# Decawave.net
KiCad netlist of a schematic drawn in Altium Designer
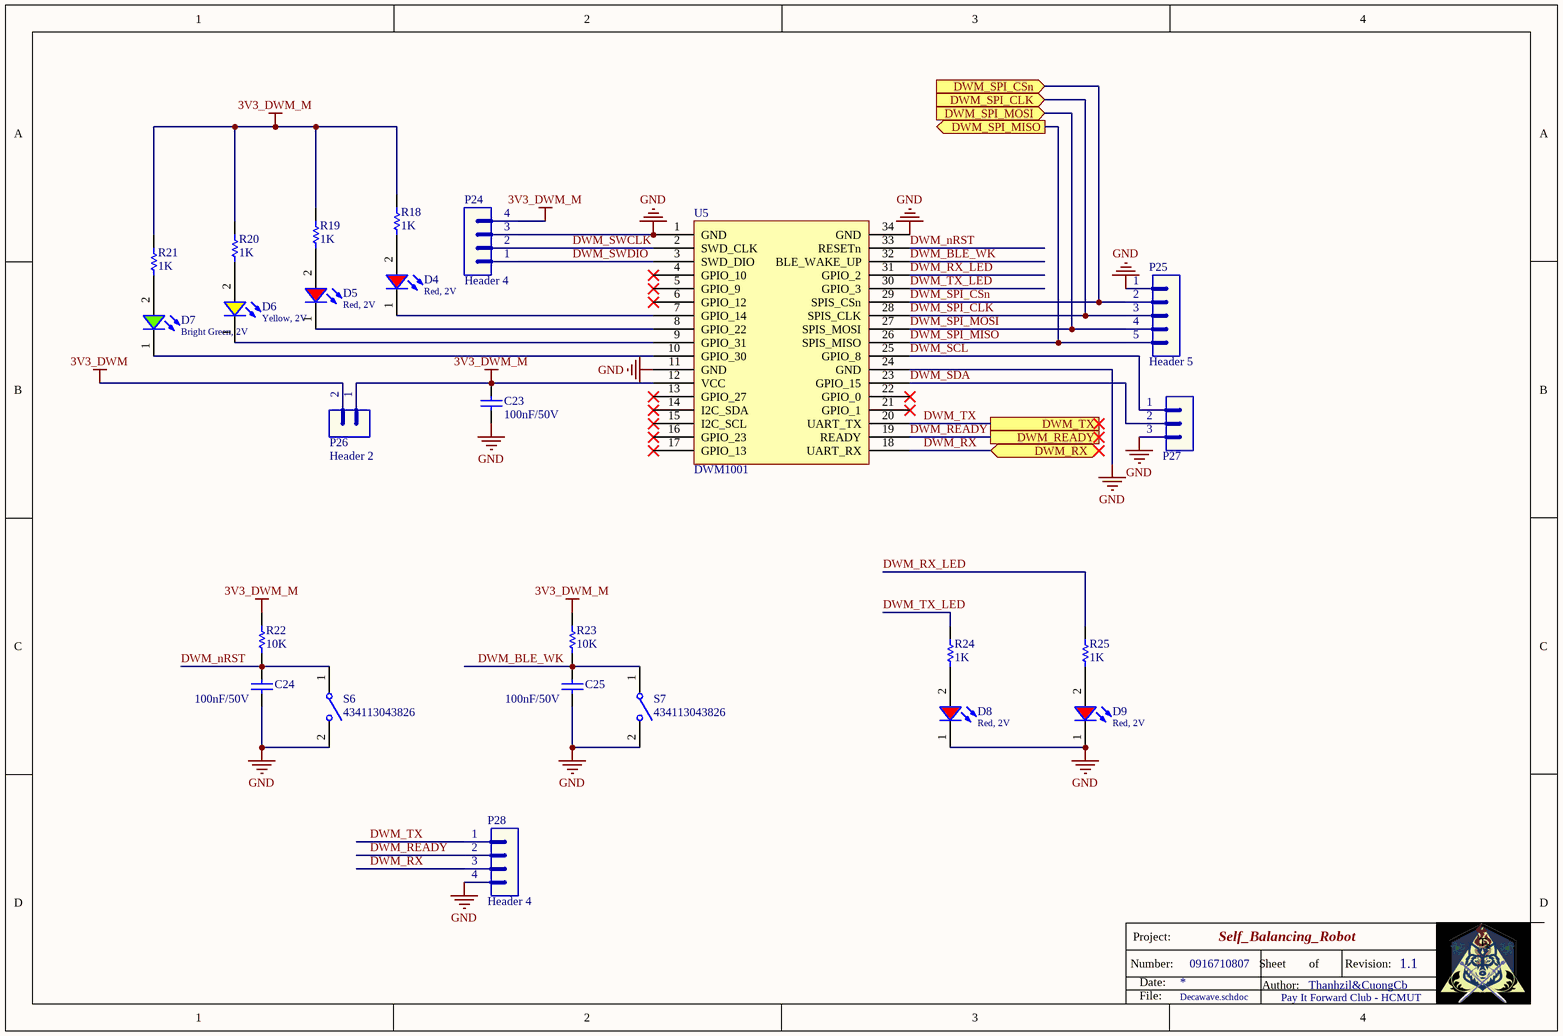
[diagram p0: Decawave.SchDoc]

(export (version "E")
  (design (tool "Eeschema 10.0.6"))
  (components
    (comp (ref "C23")
      (value "100nF/50V")
      (footprint "CAP-SM-0805")
      (description "CAP CER 0.1UF 50V Y5V 0805")
      (fields
        (field (name "MANUFACTURER") "Samsung Electro-Mechanics")
        (field (name "MANUFACTURER PART NUMBER") "CL21F104ZBCNNNC")
      )
      (libsource (lib "Capacitor") (part "Cap-100nF-50V-0805"))
    )
    (comp (ref "C24")
      (value "100nF/50V")
      (footprint "CAP-SM-0805")
      (description "CAP CER 0.1UF 50V Y5V 0805")
      (fields
        (field (name "MANUFACTURER") "Samsung Electro-Mechanics")
        (field (name "MANUFACTURER PART NUMBER") "CL21F104ZBCNNNC")
      )
      (libsource (lib "Capacitor") (part "Cap-100nF-50V-0805"))
    )
    (comp (ref "C25")
      (value "100nF/50V")
      (footprint "CAP-SM-0805")
      (description "CAP CER 0.1UF 50V Y5V 0805")
      (fields
        (field (name "MANUFACTURER") "Samsung Electro-Mechanics")
        (field (name "MANUFACTURER PART NUMBER") "CL21F104ZBCNNNC")
      )
      (libsource (lib "Capacitor") (part "Cap-100nF-50V-0805"))
    )
    (comp (ref "D4")
      (value "Red, 2V")
      (footprint "WL-SMCW_0805")
      (description "WL-SMCW SMT Mono-color Chip LED Waterclear, size 0805, Red, 2V, 140deg")
      (fields (field (name "PART NUMBER") "150080RS75000") (field (name "PUBLISHER") "Wurth Elektronik"))
      (libsource (lib "LED_150060BS75000_Altium_WL-SMCW_rev20a") (part "150080RS75000"))
    )
    (comp (ref "D5")
      (value "Red, 2V")
      (footprint "WL-SMCW_0805")
      (description "WL-SMCW SMT Mono-color Chip LED Waterclear, size 0805, Red, 2V, 140deg")
      (fields (field (name "PART NUMBER") "150080RS75000") (field (name "PUBLISHER") "Wurth Elektronik"))
      (libsource (lib "LED_150060BS75000_Altium_WL-SMCW_rev20a") (part "150080RS75000"))
    )
    (comp (ref "D6")
      (value "Yellow, 2V")
      (footprint "WL-SMCW_0805")
      (description "WL-SMCW SMT Mono-color Chip LED Waterclear, size 0805, Yellow, 2V, 140deg")
      (fields (field (name "PART NUMBER") "150080YS75000") (field (name "PUBLISHER") "Wurth Elektronik"))
      (libsource (lib "LED_150060BS75000_Altium_WL-SMCW_rev20a") (part "150080YS75000"))
    )
    (comp (ref "D7")
      (value "Bright Green, 2V")
      (footprint "WL-SMCW_0805")
      (description "WL-SMCW SMT Mono-color Chip LED Waterclear, size 0805, Bright Green, 2V, 140deg")
      (fields (field (name "PART NUMBER") "150080VS75000") (field (name "PUBLISHER") "Wurth Elektronik"))
      (libsource (lib "LED_150060BS75000_Altium_WL-SMCW_rev20a") (part "150080VS75000"))
    )
    (comp (ref "D8")
      (value "Red, 2V")
      (footprint "WL-SMCW_0805")
      (description "WL-SMCW SMT Mono-color Chip LED Waterclear, size 0805, Red, 2V, 140deg")
      (fields (field (name "PART NUMBER") "150080RS75000") (field (name "PUBLISHER") "Wurth Elektronik"))
      (libsource (lib "LED_150060BS75000_Altium_WL-SMCW_rev20a") (part "150080RS75000"))
    )
    (comp (ref "D9")
      (value "Red, 2V")
      (footprint "WL-SMCW_0805")
      (description "WL-SMCW SMT Mono-color Chip LED Waterclear, size 0805, Red, 2V, 140deg")
      (fields (field (name "PART NUMBER") "150080RS75000") (field (name "PUBLISHER") "Wurth Elektronik"))
      (libsource (lib "LED_150060BS75000_Altium_WL-SMCW_rev20a") (part "150080RS75000"))
    )
    (comp (ref "P24")
      (value "Header 4")
      (footprint "JP4")
      (description "Header, 4-Pin")
      (fields (field (name "PUBLISHER") "Altium Limited"))
      (libsource (lib "Header-connector") (part "Header 4"))
    )
    (comp (ref "P25")
      (value "Header 5")
      (footprint "JP5")
      (description "Header, 5-Pin")
      (fields (field (name "PUBLISHER") "Altium Limited"))
      (libsource (lib "Header-connector") (part "Header 5"))
    )
    (comp (ref "P26")
      (value "Header 2")
      (footprint "JP2")
      (description "Header, 2-Pin")
      (fields (field (name "PUBLISHER") "Altium Limited"))
      (libsource (lib "Header-connector") (part "Header 2"))
    )
    (comp (ref "P27")
      (value "Header 3")
      (footprint "JP3")
      (description "Header, 3-Pin")
      (fields (field (name "PUBLISHER") "Altium Limited"))
      (libsource (lib "Header-connector") (part "Header 3"))
    )
    (comp (ref "P28")
      (value "Header 4")
      (footprint "JP4")
      (description "Header, 4-Pin")
      (fields (field (name "PUBLISHER") "Altium Limited"))
      (libsource (lib "") (part "Header 4_1"))
    )
    (comp (ref "R18")
      (value "1K")
      (footprint "Resistor:RES-SM-0805")
      (description "RES 1K OHM 1% 1/4W 0805")
      (fields
        (field (name "MANUFACTURER") "Stackpole Electronics Inc")
        (field (name "MANUFACTURER PART NUMBER") "RNCP0805FTD1K00")
      )
      (libsource (lib "Resistor") (part "Res-1K-0805"))
    )
    (comp (ref "R19")
      (value "1K")
      (footprint "Resistor:RES-SM-0805")
      (description "RES 1K OHM 1% 1/4W 0805")
      (fields
        (field (name "MANUFACTURER") "Stackpole Electronics Inc")
        (field (name "MANUFACTURER PART NUMBER") "RNCP0805FTD1K00")
      )
      (libsource (lib "Resistor") (part "Res-1K-0805"))
    )
    (comp (ref "R20")
      (value "1K")
      (footprint "Resistor:RES-SM-0805")
      (description "RES 1K OHM 1% 1/4W 0805")
      (fields
        (field (name "MANUFACTURER") "Stackpole Electronics Inc")
        (field (name "MANUFACTURER PART NUMBER") "RNCP0805FTD1K00")
      )
      (libsource (lib "Resistor") (part "Res-1K-0805"))
    )
    (comp (ref "R21")
      (value "1K")
      (footprint "Resistor:RES-SM-0805")
      (description "RES 1K OHM 1% 1/4W 0805")
      (fields
        (field (name "MANUFACTURER") "Stackpole Electronics Inc")
        (field (name "MANUFACTURER PART NUMBER") "RNCP0805FTD1K00")
      )
      (libsource (lib "Resistor") (part "Res-1K-0805"))
    )
    (comp (ref "R22")
      (value "10K")
      (footprint "Resistor:RES-SM-0805")
      (description "RES 10K OHM 1% 1/4W 0805")
      (fields
        (field (name "MANUFACTURER") "Stackpole Electronics Inc")
        (field (name "MANUFACTURER PART NUMBER") "RNCP0805FTD10K0")
      )
      (libsource (lib "Resistor") (part "Res-10k-0805"))
    )
    (comp (ref "R23")
      (value "10K")
      (footprint "Resistor:RES-SM-0805")
      (description "RES 10K OHM 1% 1/4W 0805")
      (fields
        (field (name "MANUFACTURER") "Stackpole Electronics Inc")
        (field (name "MANUFACTURER PART NUMBER") "RNCP0805FTD10K0")
      )
      (libsource (lib "Resistor") (part "Res-10k-0805"))
    )
    (comp (ref "R24")
      (value "1K")
      (footprint "Resistor:RES-SM-0805")
      (description "RES 1K OHM 1% 1/4W 0805")
      (fields
        (field (name "MANUFACTURER") "Stackpole Electronics Inc")
        (field (name "MANUFACTURER PART NUMBER") "RNCP0805FTD1K00")
      )
      (libsource (lib "Resistor") (part "Res-1K-0805"))
    )
    (comp (ref "R25")
      (value "1K")
      (footprint "Resistor:RES-SM-0805")
      (description "RES 1K OHM 1% 1/4W 0805")
      (fields
        (field (name "MANUFACTURER") "Stackpole Electronics Inc")
        (field (name "MANUFACTURER PART NUMBER") "RNCP0805FTD1K00")
      )
      (libsource (lib "Resistor") (part "Res-1K-0805"))
    )
    (comp (ref "S6")
      (value "434113043826")
      (footprint "434113043826")
      (description "WS-TASV J-Bend SMT Tact Switch 6x3.5mm, height 4.3mm, 260gf")
      (fields (field (name "PUBLISHER") "Wurth Elektronik"))
      (libsource (lib "434113043826_Altium_WS-TASV_rev20a") (part "434113043826"))
    )
    (comp (ref "S7")
      (value "434113043826")
      (footprint "434113043826")
      (description "WS-TASV J-Bend SMT Tact Switch 6x3.5mm, height 4.3mm, 260gf")
      (fields (field (name "PUBLISHER") "Wurth Elektronik"))
      (libsource (lib "434113043826_Altium_WS-TASV_rev20a") (part "434113043826"))
    )
    (comp (ref "U5") (value "DWM1001") (footprint "DWM1001") (libsource (lib "PIFWRoBot") (part "DWM1001")))
  )
  (nets
    (net (code "1") (name "/DWM_BLE_WK") (class "Default")
      (node (ref "C25") (pin "1") (pinfunction "1_1") (pintype "passive"))
      (node (ref "R23") (pin "1") (pinfunction "1_1") (pintype "passive"))
      (node (ref "S7") (pin "1") (pinfunction "1_1") (pintype "passive"))
      (node (ref "U5") (pin "32") (pinfunction "BLE_WAKE_UP_32") (pintype "passive"))
    )
    (net (code "2") (name "/DWM_READY") (class "Default")
      (node (ref "P28") (pin "2") (pinfunction "2_2") (pintype "passive"))
      (node (ref "U5") (pin "19") (pinfunction "READY_19") (pintype "passive"))
    )
    (net (code "3") (name "/DWM_RX") (class "Default")
      (node (ref "P28") (pin "3") (pinfunction "3_3") (pintype "passive"))
      (node (ref "U5") (pin "18") (pinfunction "UART_RX_18") (pintype "passive"))
    )
    (net (code "4") (name "/DWM_RX_LED") (class "Default")
      (node (ref "R25") (pin "2") (pinfunction "2_2") (pintype "passive"))
      (node (ref "U5") (pin "31") (pinfunction "GPIO_2_31") (pintype "passive"))
    )
    (net (code "5") (name "/DWM_SCL") (class "Default")
      (node (ref "P27") (pin "1") (pinfunction "1_1") (pintype "passive"))
      (node (ref "U5") (pin "25") (pinfunction "GPIO_8_25") (pintype "passive"))
    )
    (net (code "6") (name "/DWM_SDA") (class "Default")
      (node (ref "P27") (pin "2") (pinfunction "2_2") (pintype "passive"))
      (node (ref "U5") (pin "23") (pinfunction "GPIO_15_23") (pintype "passive"))
    )
    (net (code "7") (name "/DWM_SPI_CLK") (class "Default")
      (node (ref "P25") (pin "3") (pinfunction "3_3") (pintype "passive"))
      (node (ref "U5") (pin "28") (pinfunction "SPIS_CLK_28") (pintype "passive"))
    )
    (net (code "8") (name "/DWM_SPI_CSn") (class "Default")
      (node (ref "P25") (pin "2") (pinfunction "2_2") (pintype "passive"))
      (node (ref "U5") (pin "29") (pinfunction "SPIS_CSn_29") (pintype "passive"))
    )
    (net (code "9") (name "/DWM_SPI_MISO") (class "Default")
      (node (ref "P25") (pin "5") (pinfunction "5_5") (pintype "passive"))
      (node (ref "U5") (pin "26") (pinfunction "SPIS_MISO_26") (pintype "passive"))
    )
    (net (code "10") (name "/DWM_SPI_MOSI") (class "Default")
      (node (ref "P25") (pin "4") (pinfunction "4_4") (pintype "passive"))
      (node (ref "U5") (pin "27") (pinfunction "SPIS_MOSI_27") (pintype "passive"))
    )
    (net (code "11") (name "/DWM_SWCLK") (class "Default")
      (node (ref "P24") (pin "2") (pinfunction "2_2") (pintype "passive"))
      (node (ref "U5") (pin "2") (pinfunction "SWD_CLK_2") (pintype "passive"))
    )
    (net (code "12") (name "/DWM_SWDIO") (class "Default")
      (node (ref "P24") (pin "1") (pinfunction "1_1") (pintype "passive"))
      (node (ref "U5") (pin "3") (pinfunction "SWD_DIO_3") (pintype "passive"))
    )
    (net (code "13") (name "/DWM_TX") (class "Default")
      (node (ref "P28") (pin "1") (pinfunction "1_1") (pintype "passive"))
      (node (ref "U5") (pin "20") (pinfunction "UART_TX_20") (pintype "passive"))
    )
    (net (code "14") (name "/DWM_TX_LED") (class "Default")
      (node (ref "R24") (pin "2") (pinfunction "2_2") (pintype "passive"))
      (node (ref "U5") (pin "30") (pinfunction "GPIO_3_30") (pintype "passive"))
    )
    (net (code "15") (name "/DWM_nRST") (class "Default")
      (node (ref "C24") (pin "1") (pinfunction "1_1") (pintype "passive"))
      (node (ref "R22") (pin "1") (pinfunction "1_1") (pintype "passive"))
      (node (ref "S6") (pin "1") (pinfunction "1_1") (pintype "passive"))
      (node (ref "U5") (pin "33") (pinfunction "RESETn_33") (pintype "passive"))
    )
    (net (code "16") (name "3V3_DWM") (class "Default")
      (node (ref "P26") (pin "2") (pinfunction "2_2") (pintype "passive"))
    )
    (net (code "17") (name "3V3_DWM_M") (class "Default")
      (node (ref "C23") (pin "2") (pinfunction "2_2") (pintype "passive"))
      (node (ref "P24") (pin "4") (pinfunction "4_4") (pintype "passive"))
      (node (ref "P26") (pin "1") (pinfunction "1_1") (pintype "passive"))
      (node (ref "R18") (pin "2") (pinfunction "2_2") (pintype "passive"))
      (node (ref "R19") (pin "2") (pinfunction "2_2") (pintype "passive"))
      (node (ref "R20") (pin "2") (pinfunction "2_2") (pintype "passive"))
      (node (ref "R21") (pin "2") (pinfunction "2_2") (pintype "passive"))
      (node (ref "R22") (pin "2") (pinfunction "2_2") (pintype "passive"))
      (node (ref "R23") (pin "2") (pinfunction "2_2") (pintype "passive"))
      (node (ref "U5") (pin "12") (pinfunction "VCC_12") (pintype "passive"))
    )
    (net (code "18") (name "GND") (class "Default")
      (node (ref "C23") (pin "1") (pinfunction "1_1") (pintype "passive"))
      (node (ref "C24") (pin "2") (pinfunction "2_2") (pintype "passive"))
      (node (ref "C25") (pin "2") (pinfunction "2_2") (pintype "passive"))
      (node (ref "D8") (pin "1") (pinfunction "K_1") (pintype "passive"))
      (node (ref "D9") (pin "1") (pinfunction "K_1") (pintype "passive"))
      (node (ref "P24") (pin "3") (pinfunction "3_3") (pintype "passive"))
      (node (ref "P25") (pin "1") (pinfunction "1_1") (pintype "passive"))
      (node (ref "P27") (pin "3") (pinfunction "3_3") (pintype "passive"))
      (node (ref "P28") (pin "4") (pinfunction "4_4") (pintype "passive"))
      (node (ref "S6") (pin "2") (pinfunction "2_2") (pintype "passive"))
      (node (ref "S7") (pin "2") (pinfunction "2_2") (pintype "passive"))
      (node (ref "U5") (pin "1") (pinfunction "GND_1") (pintype "passive"))
      (node (ref "U5") (pin "11") (pinfunction "GND_11") (pintype "passive"))
      (node (ref "U5") (pin "24") (pinfunction "GND_24") (pintype "passive"))
      (node (ref "U5") (pin "34") (pinfunction "GND_34") (pintype "passive"))
    )
    (net (code "19") (name "Net-(D4-A)") (class "Default")
      (node (ref "D4") (pin "2") (pinfunction "A_2") (pintype "passive"))
      (node (ref "R18") (pin "1") (pinfunction "1_1") (pintype "passive"))
    )
    (net (code "20") (name "Net-(D4-K)") (class "Default")
      (node (ref "D4") (pin "1") (pinfunction "K_1") (pintype "passive"))
      (node (ref "U5") (pin "7") (pinfunction "GPIO_14_7") (pintype "passive"))
    )
    (net (code "21") (name "Net-(D5-A)") (class "Default")
      (node (ref "D5") (pin "2") (pinfunction "A_2") (pintype "passive"))
      (node (ref "R19") (pin "1") (pinfunction "1_1") (pintype "passive"))
    )
    (net (code "22") (name "Net-(D5-K)") (class "Default")
      (node (ref "D5") (pin "1") (pinfunction "K_1") (pintype "passive"))
      (node (ref "U5") (pin "8") (pinfunction "GPIO_22_8") (pintype "passive"))
    )
    (net (code "23") (name "Net-(D6-A)") (class "Default")
      (node (ref "D6") (pin "2") (pinfunction "A_2") (pintype "passive"))
      (node (ref "R20") (pin "1") (pinfunction "1_1") (pintype "passive"))
    )
    (net (code "24") (name "Net-(D6-K)") (class "Default")
      (node (ref "D6") (pin "1") (pinfunction "K_1") (pintype "passive"))
      (node (ref "U5") (pin "9") (pinfunction "GPIO_31_9") (pintype "passive"))
    )
    (net (code "25") (name "Net-(D7-A)") (class "Default")
      (node (ref "D7") (pin "2") (pinfunction "A_2") (pintype "passive"))
      (node (ref "R21") (pin "1") (pinfunction "1_1") (pintype "passive"))
    )
    (net (code "26") (name "Net-(D7-K)") (class "Default")
      (node (ref "D7") (pin "1") (pinfunction "K_1") (pintype "passive"))
      (node (ref "U5") (pin "10") (pinfunction "GPIO_30_10") (pintype "passive"))
    )
    (net (code "27") (name "Net-(D8-A)") (class "Default")
      (node (ref "D8") (pin "2") (pinfunction "A_2") (pintype "passive"))
      (node (ref "R24") (pin "1") (pinfunction "1_1") (pintype "passive"))
    )
    (net (code "28") (name "Net-(D9-A)") (class "Default")
      (node (ref "D9") (pin "2") (pinfunction "A_2") (pintype "passive"))
      (node (ref "R25") (pin "1") (pinfunction "1_1") (pintype "passive"))
    )
    (net (code "29") (name "unconnected-(U5-GPIO_0-Pad22)") (class "Default")
      (node (ref "U5") (pin "22") (pinfunction "GPIO_0_22") (pintype "passive+no_connect"))
    )
    (net (code "30") (name "unconnected-(U5-GPIO_1-Pad21)") (class "Default")
      (node (ref "U5") (pin "21") (pinfunction "GPIO_1_21") (pintype "passive+no_connect"))
    )
    (net (code "31") (name "unconnected-(U5-GPIO_9-Pad5)") (class "Default")
      (node (ref "U5") (pin "5") (pinfunction "GPIO_9_5") (pintype "passive+no_connect"))
    )
    (net (code "32") (name "unconnected-(U5-GPIO_10-Pad4)") (class "Default")
      (node (ref "U5") (pin "4") (pinfunction "GPIO_10_4") (pintype "passive+no_connect"))
    )
    (net (code "33") (name "unconnected-(U5-GPIO_12-Pad6)") (class "Default")
      (node (ref "U5") (pin "6") (pinfunction "GPIO_12_6") (pintype "passive+no_connect"))
    )
    (net (code "34") (name "unconnected-(U5-GPIO_13-Pad17)") (class "Default")
      (node (ref "U5") (pin "17") (pinfunction "GPIO_13_17") (pintype "passive+no_connect"))
    )
    (net (code "35") (name "unconnected-(U5-GPIO_23-Pad16)") (class "Default")
      (node (ref "U5") (pin "16") (pinfunction "GPIO_23_16") (pintype "passive+no_connect"))
    )
    (net (code "36") (name "unconnected-(U5-GPIO_27-Pad13)") (class "Default")
      (node (ref "U5") (pin "13") (pinfunction "GPIO_27_13") (pintype "passive+no_connect"))
    )
    (net (code "37") (name "unconnected-(U5-I2C_SCL-Pad15)") (class "Default")
      (node (ref "U5") (pin "15") (pinfunction "I2C_SCL_15") (pintype "passive+no_connect"))
    )
    (net (code "38") (name "unconnected-(U5-I2C_SDA-Pad14)") (class "Default")
      (node (ref "U5") (pin "14") (pinfunction "I2C_SDA_14") (pintype "passive+no_connect"))
    )
  )
)
